# modulator.net
KiCad netlist of a schematic drawn in EAGLE
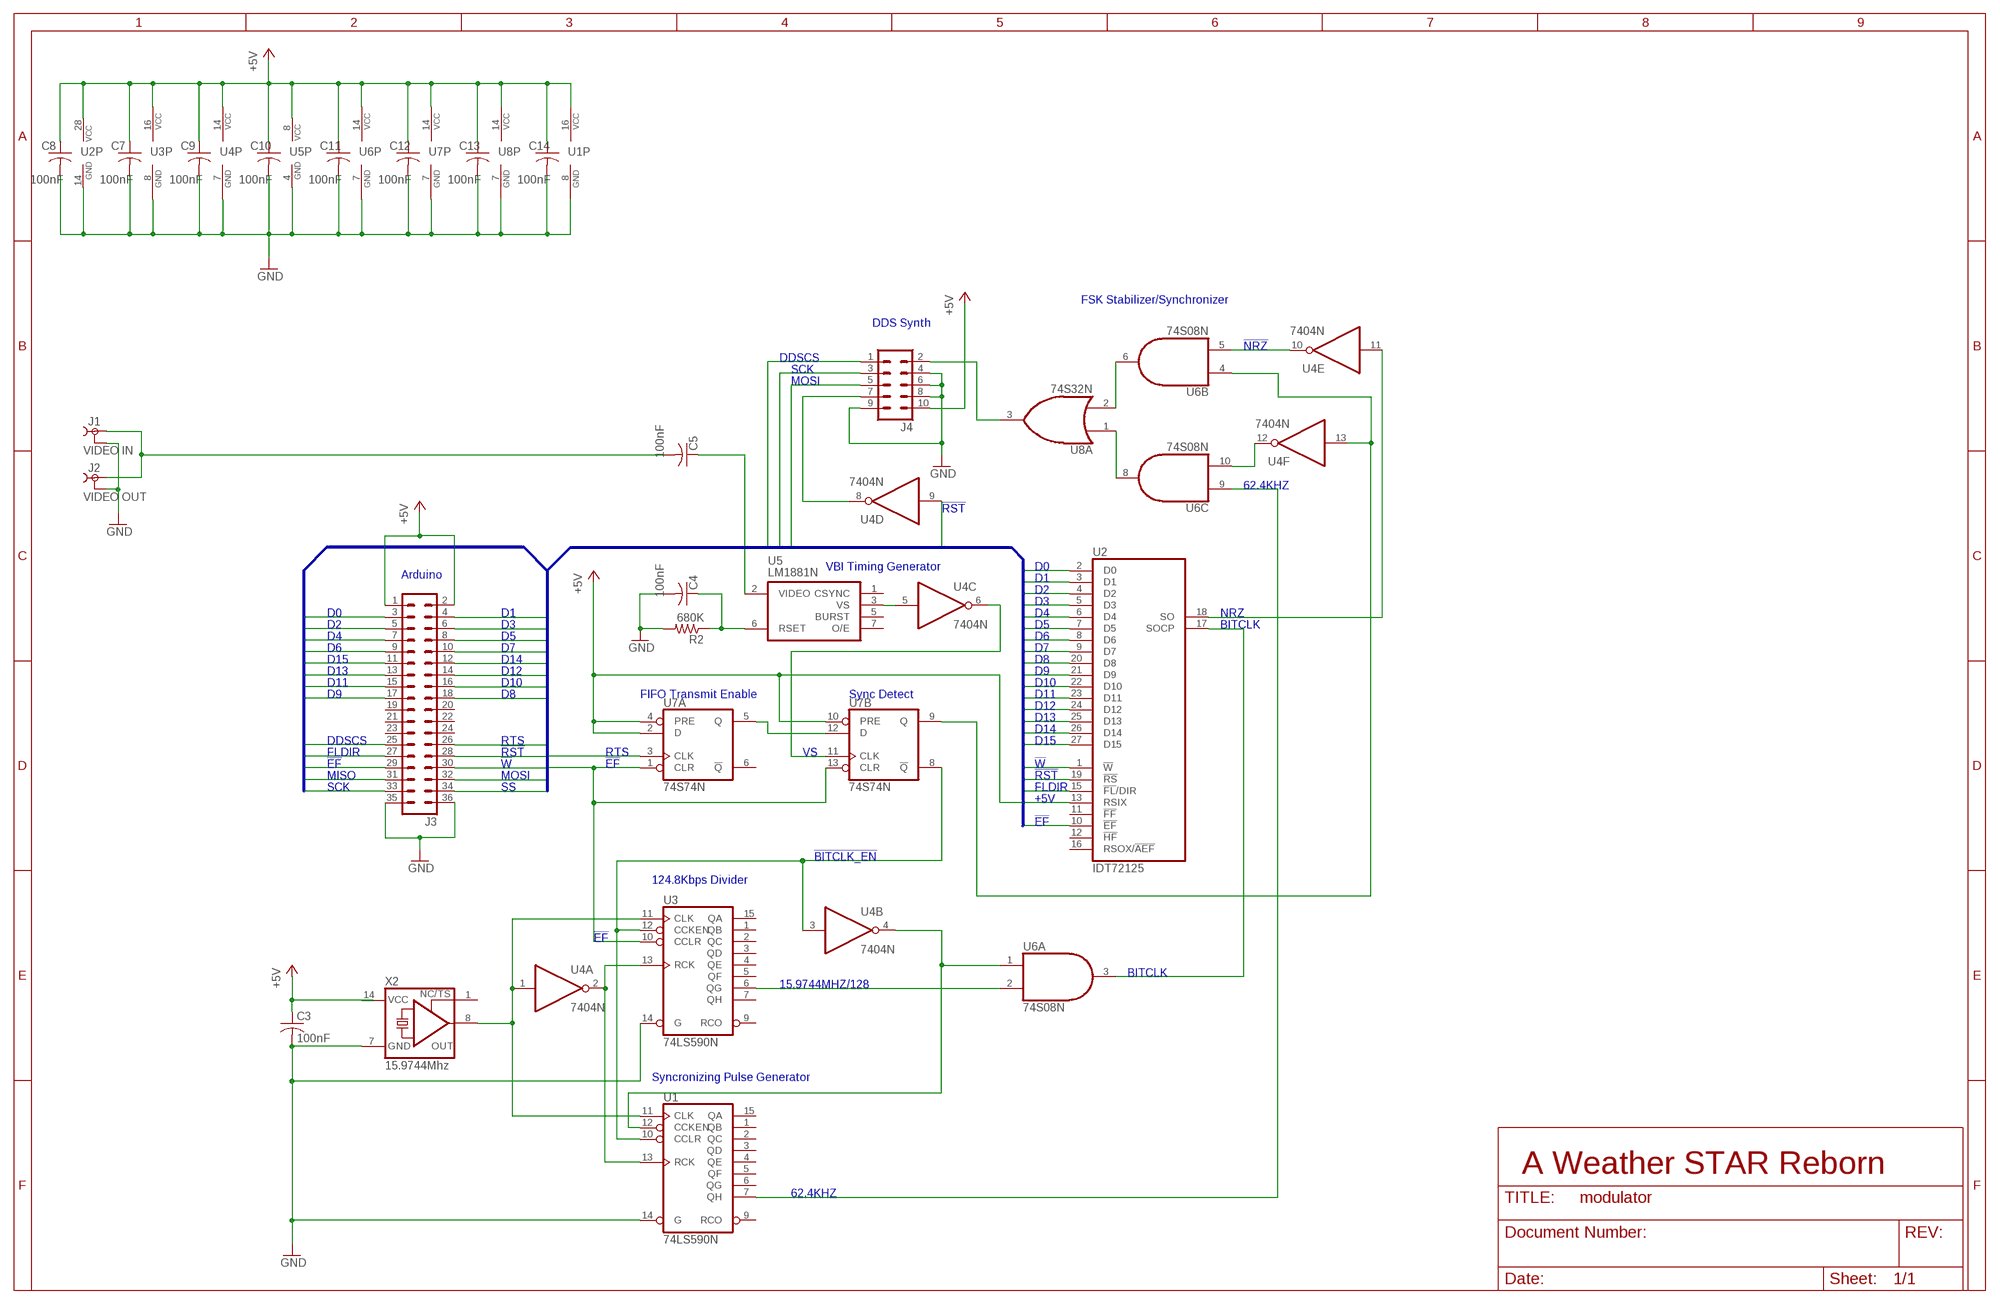
[diagram p0: schematic, sheet 1]

(export (version "E")
  (design (tool "Eeschema 10.0.6"))
  (components
    (comp (ref "C3")
      (value "100nF")
      (footprint "eagle-import:C050-025X075")
      (libsource (lib "eagle-import") (part "C-US050-025X075"))
    )
    (comp (ref "C4")
      (value "100nF")
      (footprint "eagle-import:C050-025X075")
      (libsource (lib "eagle-import") (part "C-US050-025X075"))
    )
    (comp (ref "C5")
      (value "100nF")
      (footprint "eagle-import:C050-025X075")
      (libsource (lib "eagle-import") (part "C-US050-025X075"))
    )
    (comp (ref "C7")
      (value "100nF")
      (footprint "eagle-import:C050-025X075")
      (libsource (lib "eagle-import") (part "C-US050-025X075"))
    )
    (comp (ref "C8")
      (value "100nF")
      (footprint "eagle-import:C050-025X075")
      (libsource (lib "eagle-import") (part "C-US050-025X075"))
    )
    (comp (ref "C9")
      (value "100nF")
      (footprint "eagle-import:C050-025X075")
      (libsource (lib "eagle-import") (part "C-US050-025X075"))
    )
    (comp (ref "C10")
      (value "100nF")
      (footprint "eagle-import:C050-025X075")
      (libsource (lib "eagle-import") (part "C-US050-025X075"))
    )
    (comp (ref "C11")
      (value "100nF")
      (footprint "eagle-import:C050-025X075")
      (libsource (lib "eagle-import") (part "C-US050-025X075"))
    )
    (comp (ref "C12")
      (value "100nF")
      (footprint "eagle-import:C050-025X075")
      (libsource (lib "eagle-import") (part "C-US050-025X075"))
    )
    (comp (ref "C13")
      (value "100nF")
      (footprint "eagle-import:C050-025X075")
      (libsource (lib "eagle-import") (part "C-US050-025X075"))
    )
    (comp (ref "C14")
      (value "100nF")
      (footprint "eagle-import:C050-025X075")
      (libsource (lib "eagle-import") (part "C-US050-025X075"))
    )
    (comp (ref "J1")
      (value "VIDEO IN")
      (footprint "eagle-import:TOBU3")
      (fields (field (name "MF") "FARNELL") (field (name "MPN") "TOBU 3"))
      (libsource (lib "eagle-import") (part "TOBU3"))
    )
    (comp (ref "J2")
      (value "VIDEO OUT")
      (footprint "eagle-import:TOBU3")
      (fields (field (name "MF") "FARNELL") (field (name "MPN") "TOBU 3"))
      (libsource (lib "eagle-import") (part "TOBU3"))
    )
    (comp (ref "J3")
      (value "MA18-2")
      (footprint "eagle-import:MA18-2")
      (libsource (lib "eagle-import") (part "MA18-2"))
    )
    (comp (ref "J4")
      (value "MA05-2")
      (footprint "eagle-import:MA05-2")
      (libsource (lib "eagle-import") (part "MA05-2"))
    )
    (comp (ref "R2")
      (value "680K")
      (footprint "eagle-import:0207_12")
      (libsource (lib "eagle-import") (part "R-US_0207/12"))
    )
    (comp (ref "U1")
      (value "74LS590N")
      (footprint "eagle-import:DIL16")
      (libsource (lib "eagle-import") (part "74590NLS"))
    )
    (comp (ref "U2")
      (value "IDT72125")
      (footprint "eagle-import:SO28L")
      (libsource (lib "eagle-import") (part "72125"))
    )
    (comp (ref "U3")
      (value "74LS590N")
      (footprint "eagle-import:DIL16")
      (libsource (lib "eagle-import") (part "74590NLS"))
    )
    (comp (ref "U4")
      (value "7404N")
      (footprint "eagle-import:DIL14")
      (libsource (lib "eagle-import") (part "7404N"))
    )
    (comp (ref "U5")
      (value "LM1881N")
      (footprint "eagle-import:DIL08")
      (libsource (lib "eagle-import") (part "LM1881N"))
    )
    (comp (ref "U6")
      (value "74S08N")
      (footprint "eagle-import:DIL14")
      (libsource (lib "eagle-import") (part "7408NS"))
    )
    (comp (ref "U7")
      (value "74S74N")
      (footprint "eagle-import:DIL14")
      (libsource (lib "eagle-import") (part "7474NS"))
    )
    (comp (ref "U8")
      (value "74S32N")
      (footprint "eagle-import:DIL14")
      (libsource (lib "eagle-import") (part "7432NS"))
    )
    (comp (ref "X2")
      (value "15.9744Mhz")
      (footprint "eagle-import:DIL14S")
      (libsource (lib "eagle-import") (part "XO-14"))
    )
  )
  (nets
    (net (code "1") (name "+5V") (class "Default")
      (node (ref "C10") (pin "1") (pinfunction "1_1") (pintype "passive"))
      (node (ref "C11") (pin "1") (pinfunction "1_1") (pintype "passive"))
      (node (ref "C12") (pin "1") (pinfunction "1_1") (pintype "passive"))
      (node (ref "C13") (pin "1") (pinfunction "1_1") (pintype "passive"))
      (node (ref "C14") (pin "1") (pinfunction "1_1") (pintype "passive"))
      (node (ref "C3") (pin "1") (pinfunction "1_1") (pintype "passive"))
      (node (ref "C7") (pin "1") (pinfunction "1_1") (pintype "passive"))
      (node (ref "C8") (pin "1") (pinfunction "1_1") (pintype "passive"))
      (node (ref "C9") (pin "1") (pinfunction "1_1") (pintype "passive"))
      (node (ref "J3") (pin "1") (pinfunction "1_1") (pintype "passive"))
      (node (ref "J3") (pin "2") (pinfunction "2_2") (pintype "passive"))
      (node (ref "J4") (pin "10") (pinfunction "10_10") (pintype "passive"))
      (node (ref "U1") (pin "16") (pinfunction "VCC_16") (pintype "power_in"))
      (node (ref "U2") (pin "13") (pinfunction "RSIX_13") (pintype "input"))
      (node (ref "U2") (pin "28") (pinfunction "VCC_28") (pintype "power_in"))
      (node (ref "U3") (pin "16") (pinfunction "VCC_16") (pintype "power_in"))
      (node (ref "U4") (pin "14") (pinfunction "VCC_14") (pintype "power_in"))
      (node (ref "U5") (pin "8") (pinfunction "VCC_8") (pintype "power_in"))
      (node (ref "U6") (pin "14") (pinfunction "VCC_14") (pintype "power_in"))
      (node (ref "U7") (pin "10") (pinfunction "PRE_10") (pintype "input"))
      (node (ref "U7") (pin "14") (pinfunction "VCC_14") (pintype "power_in"))
      (node (ref "U7") (pin "2") (pinfunction "D_2") (pintype "input"))
      (node (ref "U7") (pin "4") (pinfunction "PRE_4") (pintype "input"))
      (node (ref "U8") (pin "14") (pinfunction "VCC_14") (pintype "power_in"))
      (node (ref "X2") (pin "14") (pinfunction "VCC_14") (pintype "power_in"))
    )
    (net (code "2") (name "/15.9744MHZ{slash}128") (class "Default")
      (node (ref "U3") (pin "6") (pinfunction "QG_6") (pintype "tri_state"))
      (node (ref "U6") (pin "2") (pinfunction "I1_2") (pintype "input"))
    )
    (net (code "3") (name "/62.4KHZ") (class "Default")
      (node (ref "U1") (pin "7") (pinfunction "QH_7") (pintype "tri_state"))
      (node (ref "U6") (pin "9") (pinfunction "I0_9") (pintype "input"))
    )
    (net (code "4") (name "/BITCLK") (class "Default")
      (node (ref "U2") (pin "17") (pinfunction "SOCP_17") (pintype "input"))
      (node (ref "U6") (pin "3") (pinfunction "O_3") (pintype "output"))
    )
    (net (code "5") (name "/D0") (class "Default")
      (node (ref "J3") (pin "3") (pinfunction "3_3") (pintype "passive"))
      (node (ref "U2") (pin "2") (pinfunction "D0_2") (pintype "input"))
    )
    (net (code "6") (name "/D1") (class "Default")
      (node (ref "J3") (pin "4") (pinfunction "4_4") (pintype "passive"))
      (node (ref "U2") (pin "3") (pinfunction "D1_3") (pintype "input"))
    )
    (net (code "7") (name "/D2") (class "Default")
      (node (ref "J3") (pin "5") (pinfunction "5_5") (pintype "passive"))
      (node (ref "U2") (pin "4") (pinfunction "D2_4") (pintype "input"))
    )
    (net (code "8") (name "/D3") (class "Default")
      (node (ref "J3") (pin "6") (pinfunction "6_6") (pintype "passive"))
      (node (ref "U2") (pin "5") (pinfunction "D3_5") (pintype "input"))
    )
    (net (code "9") (name "/D4") (class "Default")
      (node (ref "J3") (pin "7") (pinfunction "7_7") (pintype "passive"))
      (node (ref "U2") (pin "6") (pinfunction "D4_6") (pintype "input"))
    )
    (net (code "10") (name "/D5") (class "Default")
      (node (ref "J3") (pin "8") (pinfunction "8_8") (pintype "passive"))
      (node (ref "U2") (pin "7") (pinfunction "D5_7") (pintype "input"))
    )
    (net (code "11") (name "/D6") (class "Default")
      (node (ref "J3") (pin "9") (pinfunction "9_9") (pintype "passive"))
      (node (ref "U2") (pin "8") (pinfunction "D6_8") (pintype "input"))
    )
    (net (code "12") (name "/D7") (class "Default")
      (node (ref "J3") (pin "10") (pinfunction "10_10") (pintype "passive"))
      (node (ref "U2") (pin "9") (pinfunction "D7_9") (pintype "input"))
    )
    (net (code "13") (name "/D8") (class "Default")
      (node (ref "J3") (pin "18") (pinfunction "18_18") (pintype "passive"))
      (node (ref "U2") (pin "20") (pinfunction "D8_20") (pintype "input"))
    )
    (net (code "14") (name "/D9") (class "Default")
      (node (ref "J3") (pin "17") (pinfunction "17_17") (pintype "passive"))
      (node (ref "U2") (pin "21") (pinfunction "D9_21") (pintype "input"))
    )
    (net (code "15") (name "/D10") (class "Default")
      (node (ref "J3") (pin "16") (pinfunction "16_16") (pintype "passive"))
      (node (ref "U2") (pin "22") (pinfunction "D10_22") (pintype "input"))
    )
    (net (code "16") (name "/D11") (class "Default")
      (node (ref "J3") (pin "15") (pinfunction "15_15") (pintype "passive"))
      (node (ref "U2") (pin "23") (pinfunction "D11_23") (pintype "input"))
    )
    (net (code "17") (name "/D12") (class "Default")
      (node (ref "J3") (pin "14") (pinfunction "14_14") (pintype "passive"))
      (node (ref "U2") (pin "24") (pinfunction "D12_24") (pintype "input"))
    )
    (net (code "18") (name "/D13") (class "Default")
      (node (ref "J3") (pin "13") (pinfunction "13_13") (pintype "passive"))
      (node (ref "U2") (pin "25") (pinfunction "D13_25") (pintype "input"))
    )
    (net (code "19") (name "/D14") (class "Default")
      (node (ref "J3") (pin "12") (pinfunction "12_12") (pintype "passive"))
      (node (ref "U2") (pin "26") (pinfunction "D14_26") (pintype "input"))
    )
    (net (code "20") (name "/D15") (class "Default")
      (node (ref "J3") (pin "11") (pinfunction "11_11") (pintype "passive"))
      (node (ref "U2") (pin "27") (pinfunction "D15_27") (pintype "input"))
    )
    (net (code "21") (name "/DDSCS") (class "Default")
      (node (ref "J3") (pin "25") (pinfunction "25_25") (pintype "passive"))
      (node (ref "J4") (pin "1") (pinfunction "1_1") (pintype "passive"))
    )
    (net (code "22") (name "/FLDIR") (class "Default")
      (node (ref "J3") (pin "27") (pinfunction "27_27") (pintype "passive"))
      (node (ref "U2") (pin "15") (pinfunction "~{FL}/DIR_15") (pintype "input"))
    )
    (net (code "23") (name "/MISO") (class "Default")
      (node (ref "J3") (pin "31") (pinfunction "31_31") (pintype "passive"))
    )
    (net (code "24") (name "/MOSI") (class "Default")
      (node (ref "J3") (pin "32") (pinfunction "32_32") (pintype "passive"))
      (node (ref "J4") (pin "5") (pinfunction "5_5") (pintype "passive"))
    )
    (net (code "25") (name "/NRZ") (class "Default")
      (node (ref "U2") (pin "18") (pinfunction "SO_18") (pintype "output"))
      (node (ref "U4") (pin "11") (pinfunction "I_11") (pintype "input"))
    )
    (net (code "26") (name "/RTS") (class "Default")
      (node (ref "J3") (pin "26") (pinfunction "26_26") (pintype "passive"))
      (node (ref "U7") (pin "3") (pinfunction "CLK_3") (pintype "input"))
    )
    (net (code "27") (name "/SCK") (class "Default")
      (node (ref "J3") (pin "33") (pinfunction "33_33") (pintype "passive"))
      (node (ref "J4") (pin "3") (pinfunction "3_3") (pintype "passive"))
    )
    (net (code "28") (name "/SS") (class "Default")
      (node (ref "J3") (pin "34") (pinfunction "34_34") (pintype "passive"))
    )
    (net (code "29") (name "/VS") (class "Default")
      (node (ref "U4") (pin "6") (pinfunction "O_6") (pintype "output"))
      (node (ref "U7") (pin "11") (pinfunction "CLK_11") (pintype "input"))
    )
    (net (code "30") (name "/~{BITCLK_EN}") (class "Default")
      (node (ref "U1") (pin "10") (pinfunction "CCLR_10") (pintype "input"))
      (node (ref "U3") (pin "12") (pinfunction "CCKEN_12") (pintype "input"))
      (node (ref "U4") (pin "3") (pinfunction "I_3") (pintype "input"))
      (node (ref "U7") (pin "8") (pinfunction "~{Q}_8") (pintype "output"))
    )
    (net (code "31") (name "/~{EF}") (class "Default")
      (node (ref "J3") (pin "29") (pinfunction "29_29") (pintype "passive"))
      (node (ref "U2") (pin "10") (pinfunction "~{EF}_10") (pintype "output"))
      (node (ref "U3") (pin "10") (pinfunction "CCLR_10") (pintype "input"))
      (node (ref "U7") (pin "1") (pinfunction "CLR_1") (pintype "input"))
      (node (ref "U7") (pin "13") (pinfunction "CLR_13") (pintype "input"))
    )
    (net (code "32") (name "/~{NRZ}") (class "Default")
      (node (ref "U4") (pin "10") (pinfunction "O_10") (pintype "output"))
      (node (ref "U6") (pin "5") (pinfunction "I1_5") (pintype "input"))
    )
    (net (code "33") (name "/~{RST}") (class "Default")
      (node (ref "J3") (pin "28") (pinfunction "28_28") (pintype "passive"))
      (node (ref "U2") (pin "19") (pinfunction "~{RS}_19") (pintype "input"))
      (node (ref "U4") (pin "9") (pinfunction "I_9") (pintype "input"))
    )
    (net (code "34") (name "/~{W}") (class "Default")
      (node (ref "J3") (pin "30") (pinfunction "30_30") (pintype "passive"))
      (node (ref "U2") (pin "1") (pinfunction "~{W}_1") (pintype "input"))
    )
    (net (code "35") (name "GND") (class "Default")
      (node (ref "C10") (pin "2") (pinfunction "2_2") (pintype "passive"))
      (node (ref "C11") (pin "2") (pinfunction "2_2") (pintype "passive"))
      (node (ref "C12") (pin "2") (pinfunction "2_2") (pintype "passive"))
      (node (ref "C13") (pin "2") (pinfunction "2_2") (pintype "passive"))
      (node (ref "C14") (pin "2") (pinfunction "2_2") (pintype "passive"))
      (node (ref "C3") (pin "2") (pinfunction "2_2") (pintype "passive"))
      (node (ref "C4") (pin "2") (pinfunction "2_2") (pintype "passive"))
      (node (ref "C7") (pin "2") (pinfunction "2_2") (pintype "passive"))
      (node (ref "C8") (pin "2") (pinfunction "2_2") (pintype "passive"))
      (node (ref "C9") (pin "2") (pinfunction "2_2") (pintype "passive"))
      (node (ref "J1") (pin "2") (pinfunction "2_2") (pintype "passive"))
      (node (ref "J1") (pin "2@1") (pinfunction "2_2@1") (pintype "passive"))
      (node (ref "J1") (pin "2@2") (pinfunction "2_2@2") (pintype "passive"))
      (node (ref "J2") (pin "2") (pinfunction "2_2") (pintype "passive"))
      (node (ref "J2") (pin "2@1") (pinfunction "2_2@1") (pintype "passive"))
      (node (ref "J2") (pin "2@2") (pinfunction "2_2@2") (pintype "passive"))
      (node (ref "J3") (pin "35") (pinfunction "35_35") (pintype "passive"))
      (node (ref "J3") (pin "36") (pinfunction "36_36") (pintype "passive"))
      (node (ref "J4") (pin "4") (pinfunction "4_4") (pintype "passive"))
      (node (ref "J4") (pin "6") (pinfunction "6_6") (pintype "passive"))
      (node (ref "J4") (pin "8") (pinfunction "8_8") (pintype "passive"))
      (node (ref "J4") (pin "9") (pinfunction "9_9") (pintype "passive"))
      (node (ref "R2") (pin "2") (pinfunction "2_2") (pintype "passive"))
      (node (ref "U1") (pin "14") (pinfunction "G_14") (pintype "input"))
      (node (ref "U1") (pin "8") (pinfunction "GND_8") (pintype "power_in"))
      (node (ref "U2") (pin "14") (pinfunction "GND_14") (pintype "power_in"))
      (node (ref "U3") (pin "14") (pinfunction "G_14") (pintype "input"))
      (node (ref "U3") (pin "8") (pinfunction "GND_8") (pintype "power_in"))
      (node (ref "U4") (pin "7") (pinfunction "GND_7") (pintype "power_in"))
      (node (ref "U5") (pin "4") (pinfunction "GND_4") (pintype "power_in"))
      (node (ref "U6") (pin "7") (pinfunction "GND_7") (pintype "power_in"))
      (node (ref "U7") (pin "7") (pinfunction "GND_7") (pintype "power_in"))
      (node (ref "U8") (pin "7") (pinfunction "GND_7") (pintype "power_in"))
      (node (ref "X2") (pin "7") (pinfunction "GND_7") (pintype "power_in"))
    )
    (net (code "36") (name "Net-(C5-Pad2)") (class "Default")
      (node (ref "C5") (pin "2") (pinfunction "2_2") (pintype "passive"))
      (node (ref "J1") (pin "1") (pinfunction "1_1") (pintype "passive"))
      (node (ref "J2") (pin "1") (pinfunction "1_1") (pintype "passive"))
    )
    (net (code "37") (name "Net-(U1A-CCKEN)") (class "Default")
      (node (ref "U1") (pin "12") (pinfunction "CCKEN_12") (pintype "input"))
      (node (ref "U4") (pin "4") (pinfunction "O_4") (pintype "output"))
      (node (ref "U6") (pin "1") (pinfunction "I0_1") (pintype "input"))
    )
    (net (code "38") (name "Net-(U1A-CLK)") (class "Default")
      (node (ref "U1") (pin "11") (pinfunction "CLK_11") (pintype "input"))
      (node (ref "U3") (pin "11") (pinfunction "CLK_11") (pintype "input"))
      (node (ref "U4") (pin "1") (pinfunction "I_1") (pintype "input"))
      (node (ref "X2") (pin "8") (pinfunction "OUT_8") (pintype "output"))
    )
    (net (code "39") (name "Net-(U1A-RCK)") (class "Default")
      (node (ref "U1") (pin "13") (pinfunction "RCK_13") (pintype "input"))
      (node (ref "U3") (pin "13") (pinfunction "RCK_13") (pintype "input"))
      (node (ref "U4") (pin "2") (pinfunction "O_2") (pintype "output"))
    )
    (net (code "40") (name "Net-(U4C-I)") (class "Default")
      (node (ref "U4") (pin "5") (pinfunction "I_5") (pintype "input"))
      (node (ref "U5") (pin "3") (pinfunction "VS_3") (pintype "output"))
    )
    (net (code "41") (name "Net-(U4D-O)") (class "Default")
      (node (ref "J4") (pin "7") (pinfunction "7_7") (pintype "passive"))
      (node (ref "U4") (pin "8") (pinfunction "O_8") (pintype "output"))
    )
    (net (code "42") (name "Net-(U4F-I)") (class "Default")
      (node (ref "U4") (pin "13") (pinfunction "I_13") (pintype "input"))
      (node (ref "U6") (pin "4") (pinfunction "I0_4") (pintype "input"))
      (node (ref "U7") (pin "9") (pinfunction "Q_9") (pintype "output"))
    )
    (net (code "43") (name "Net-(U4F-O)") (class "Default")
      (node (ref "U4") (pin "12") (pinfunction "O_12") (pintype "output"))
      (node (ref "U6") (pin "10") (pinfunction "I1_10") (pintype "input"))
    )
    (net (code "44") (name "Net-(U5A-RSET)") (class "Default")
      (node (ref "C4") (pin "1") (pinfunction "1_1") (pintype "passive"))
      (node (ref "R2") (pin "1") (pinfunction "1_1") (pintype "passive"))
      (node (ref "U5") (pin "6") (pinfunction "RSET_6") (pintype "passive"))
    )
    (net (code "45") (name "Net-(U5A-VIDEO)") (class "Default")
      (node (ref "C5") (pin "1") (pinfunction "1_1") (pintype "passive"))
      (node (ref "U5") (pin "2") (pinfunction "VIDEO_2") (pintype "input"))
    )
    (net (code "46") (name "Net-(U6B-O)") (class "Default")
      (node (ref "U6") (pin "6") (pinfunction "O_6") (pintype "output"))
      (node (ref "U8") (pin "2") (pinfunction "I1_2") (pintype "input"))
    )
    (net (code "47") (name "Net-(U6C-O)") (class "Default")
      (node (ref "U6") (pin "8") (pinfunction "O_8") (pintype "output"))
      (node (ref "U8") (pin "1") (pinfunction "I0_1") (pintype "input"))
    )
    (net (code "48") (name "Net-(U7A-Q)") (class "Default")
      (node (ref "U7") (pin "12") (pinfunction "D_12") (pintype "input"))
      (node (ref "U7") (pin "5") (pinfunction "Q_5") (pintype "output"))
    )
    (net (code "49") (name "Net-(U8A-O)") (class "Default")
      (node (ref "J4") (pin "2") (pinfunction "2_2") (pintype "passive"))
      (node (ref "U8") (pin "3") (pinfunction "O_3") (pintype "output"))
    )
    (net (code "50") (name "unconnected-(J3-Pad19)") (class "Default")
      (node (ref "J3") (pin "19") (pinfunction "19_19") (pintype "passive"))
    )
    (net (code "51") (name "unconnected-(J3-Pad20)") (class "Default")
      (node (ref "J3") (pin "20") (pinfunction "20_20") (pintype "passive"))
    )
    (net (code "52") (name "unconnected-(J3-Pad21)") (class "Default")
      (node (ref "J3") (pin "21") (pinfunction "21_21") (pintype "passive"))
    )
    (net (code "53") (name "unconnected-(J3-Pad22)") (class "Default")
      (node (ref "J3") (pin "22") (pinfunction "22_22") (pintype "passive"))
    )
    (net (code "54") (name "unconnected-(J3-Pad23)") (class "Default")
      (node (ref "J3") (pin "23") (pinfunction "23_23") (pintype "passive"))
    )
    (net (code "55") (name "unconnected-(J3-Pad24)") (class "Default")
      (node (ref "J3") (pin "24") (pinfunction "24_24") (pintype "passive"))
    )
    (net (code "56") (name "unconnected-(U1A-QA-Pad15)") (class "Default")
      (node (ref "U1") (pin "15") (pinfunction "QA_15") (pintype "tri_state"))
    )
    (net (code "57") (name "unconnected-(U1A-QB-Pad1)") (class "Default")
      (node (ref "U1") (pin "1") (pinfunction "QB_1") (pintype "tri_state"))
    )
    (net (code "58") (name "unconnected-(U1A-QC-Pad2)") (class "Default")
      (node (ref "U1") (pin "2") (pinfunction "QC_2") (pintype "tri_state"))
    )
    (net (code "59") (name "unconnected-(U1A-QD-Pad3)") (class "Default")
      (node (ref "U1") (pin "3") (pinfunction "QD_3") (pintype "tri_state"))
    )
    (net (code "60") (name "unconnected-(U1A-QE-Pad4)") (class "Default")
      (node (ref "U1") (pin "4") (pinfunction "QE_4") (pintype "tri_state"))
    )
    (net (code "61") (name "unconnected-(U1A-QF-Pad5)") (class "Default")
      (node (ref "U1") (pin "5") (pinfunction "QF_5") (pintype "tri_state"))
    )
    (net (code "62") (name "unconnected-(U1A-QG-Pad6)") (class "Default")
      (node (ref "U1") (pin "6") (pinfunction "QG_6") (pintype "tri_state"))
    )
    (net (code "63") (name "unconnected-(U1A-RCO-Pad9)") (class "Default")
      (node (ref "U1") (pin "9") (pinfunction "RCO_9") (pintype "output"))
    )
    (net (code "64") (name "unconnected-(U2A-RSOX{slash}~{AEF}-Pad16)") (class "Default")
      (node (ref "U2") (pin "16") (pinfunction "RSOX/~{AEF}_16") (pintype "output"))
    )
    (net (code "65") (name "unconnected-(U2A-~{FF}-Pad11)") (class "Default")
      (node (ref "U2") (pin "11") (pinfunction "~{FF}_11") (pintype "output"))
    )
    (net (code "66") (name "unconnected-(U2A-~{HF}-Pad12)") (class "Default")
      (node (ref "U2") (pin "12") (pinfunction "~{HF}_12") (pintype "output"))
    )
    (net (code "67") (name "unconnected-(U3A-QA-Pad15)") (class "Default")
      (node (ref "U3") (pin "15") (pinfunction "QA_15") (pintype "tri_state"))
    )
    (net (code "68") (name "unconnected-(U3A-QB-Pad1)") (class "Default")
      (node (ref "U3") (pin "1") (pinfunction "QB_1") (pintype "tri_state"))
    )
    (net (code "69") (name "unconnected-(U3A-QC-Pad2)") (class "Default")
      (node (ref "U3") (pin "2") (pinfunction "QC_2") (pintype "tri_state"))
    )
    (net (code "70") (name "unconnected-(U3A-QD-Pad3)") (class "Default")
      (node (ref "U3") (pin "3") (pinfunction "QD_3") (pintype "tri_state"))
    )
    (net (code "71") (name "unconnected-(U3A-QE-Pad4)") (class "Default")
      (node (ref "U3") (pin "4") (pinfunction "QE_4") (pintype "tri_state"))
    )
    (net (code "72") (name "unconnected-(U3A-QF-Pad5)") (class "Default")
      (node (ref "U3") (pin "5") (pinfunction "QF_5") (pintype "tri_state"))
    )
    (net (code "73") (name "unconnected-(U3A-QH-Pad7)") (class "Default")
      (node (ref "U3") (pin "7") (pinfunction "QH_7") (pintype "tri_state"))
    )
    (net (code "74") (name "unconnected-(U3A-RCO-Pad9)") (class "Default")
      (node (ref "U3") (pin "9") (pinfunction "RCO_9") (pintype "output"))
    )
    (net (code "75") (name "unconnected-(U5A-BURST-Pad5)") (class "Default")
      (node (ref "U5") (pin "5") (pinfunction "BURST_5") (pintype "output"))
    )
    (net (code "76") (name "unconnected-(U5A-CSYNC-Pad1)") (class "Default")
      (node (ref "U5") (pin "1") (pinfunction "CSYNC_1") (pintype "output"))
    )
    (net (code "77") (name "unconnected-(U5A-O{slash}E-Pad7)") (class "Default")
      (node (ref "U5") (pin "7") (pinfunction "O/E_7") (pintype "output"))
    )
    (net (code "78") (name "unconnected-(U7A-~{Q}-Pad6)") (class "Default")
      (node (ref "U7") (pin "6") (pinfunction "~{Q}_6") (pintype "output"))
    )
    (net (code "79") (name "unconnected-(X2-TS-Pad1)") (class "Default")
      (node (ref "X2") (pin "1") (pinfunction "TS_1") (pintype "passive"))
    )
  )
)
